# PCB_v1.net
KiCad netlist of a schematic drawn in EAGLE
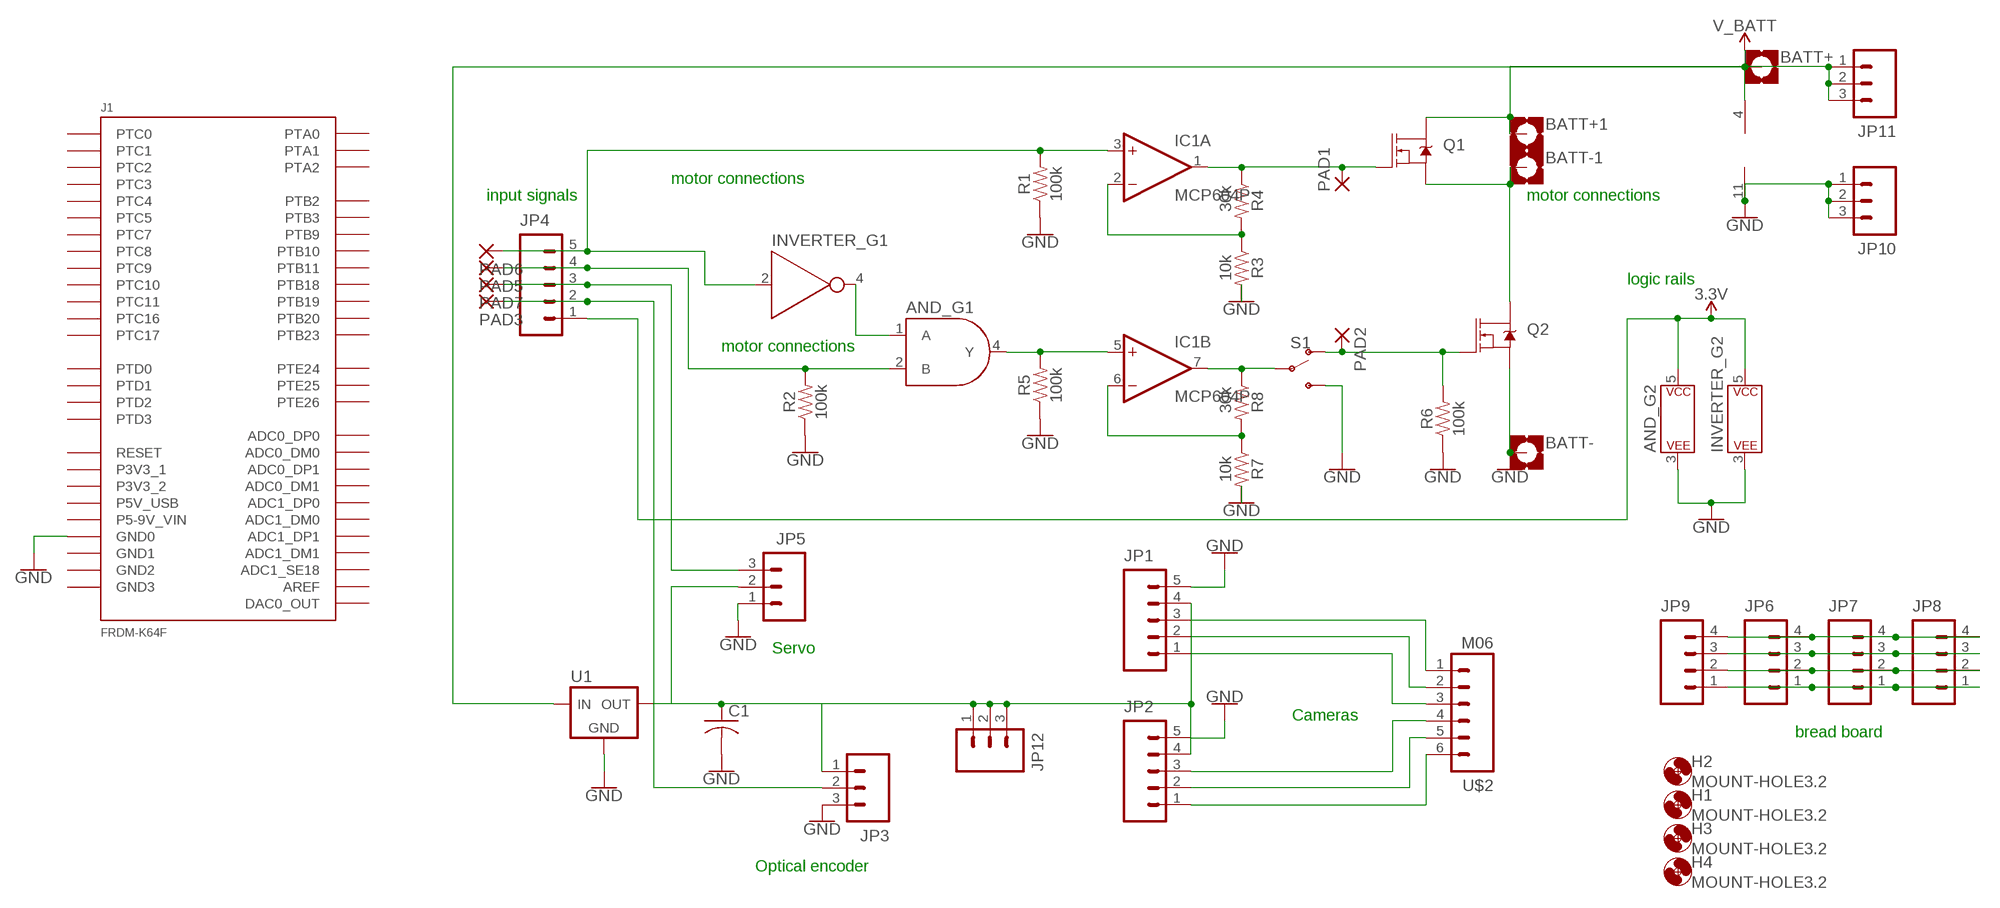
[diagram p0: schematic, sheet 1]

(export (version "E")
  (design (tool "Eeschema 10.0.6"))
  (components
    (comp (ref "AND_")
      (value "74LVC08SE")
      (footprint "eagle-import:SOT23-5")
      (libsource (lib "eagle-import") (part "7408SELVC"))
    )
    (comp (ref "BATT+")
      (value "MOUNT-PAD-SQUARE3.0")
      (footprint "eagle-import:3,0-PAD-SQUARE")
      (libsource (lib "eagle-import") (part "MOUNT-PAD-SQUARE3.0"))
    )
    (comp (ref "BATT+1")
      (value "MOUNT-PAD-SQUARE3.0")
      (footprint "eagle-import:3,0-PAD-SQUARE")
      (libsource (lib "eagle-import") (part "MOUNT-PAD-SQUARE3.0"))
    )
    (comp (ref "BATT-")
      (value "MOUNT-PAD-SQUARE3.0")
      (footprint "eagle-import:3,0-PAD-SQUARE")
      (libsource (lib "eagle-import") (part "MOUNT-PAD-SQUARE3.0"))
    )
    (comp (ref "BATT-1")
      (value "MOUNT-PAD-SQUARE3.0")
      (footprint "eagle-import:3,0-PAD-SQUARE")
      (libsource (lib "eagle-import") (part "MOUNT-PAD-SQUARE3.0"))
    )
    (comp (ref "C1")
      (value "C-075PTH")
      (footprint "eagle-import:C075")
      (libsource (lib "eagle-import") (part "C-075PTH"))
    )
    (comp (ref "H1")
      (value "MOUNT-HOLE3.2")
      (footprint "eagle-import:3,2")
      (libsource (lib "eagle-import") (part "MOUNT-HOLE3.2"))
    )
    (comp (ref "H2")
      (value "MOUNT-HOLE3.2")
      (footprint "eagle-import:3,2")
      (libsource (lib "eagle-import") (part "MOUNT-HOLE3.2"))
    )
    (comp (ref "H3")
      (value "MOUNT-HOLE3.2")
      (footprint "eagle-import:3,2")
      (libsource (lib "eagle-import") (part "MOUNT-HOLE3.2"))
    )
    (comp (ref "H4")
      (value "MOUNT-HOLE3.2")
      (footprint "eagle-import:3,2")
      (libsource (lib "eagle-import") (part "MOUNT-HOLE3.2"))
    )
    (comp (ref "IC1")
      (value "MCP604P")
      (footprint "eagle-import:DIL14")
      (libsource (lib "eagle-import") (part "MCP604P"))
    )
    (comp (ref "INVERTER_")
      (value "74HC1G04")
      (footprint "eagle-import:SOT353")
      (libsource (lib "eagle-import") (part "741G04HC"))
    )
    (comp (ref "J1")
      (value "FRDM-K64F")
      (footprint "eagle-import:FRDM-K64F")
      (libsource (lib "eagle-import") (part "FRDM-K64F"))
    )
    (comp (ref "JP1")
      (value "M05PTH")
      (footprint "eagle-import:1X05")
      (libsource (lib "eagle-import") (part "M05PTH"))
    )
    (comp (ref "JP2")
      (value "M05PTH")
      (footprint "eagle-import:1X05")
      (libsource (lib "eagle-import") (part "M05PTH"))
    )
    (comp (ref "JP3")
      (value "M03PTH")
      (footprint "eagle-import:1X03")
      (libsource (lib "eagle-import") (part "M03PTH"))
    )
    (comp (ref "JP4")
      (value "M05PTH")
      (footprint "eagle-import:1X05")
      (libsource (lib "eagle-import") (part "M05PTH"))
    )
    (comp (ref "JP5")
      (value "M03PTH")
      (footprint "eagle-import:1X03")
      (libsource (lib "eagle-import") (part "M03PTH"))
    )
    (comp (ref "JP6")
      (value "M04PTH")
      (footprint "eagle-import:1X04")
      (libsource (lib "eagle-import") (part "M04PTH"))
    )
    (comp (ref "JP7")
      (value "M04PTH")
      (footprint "eagle-import:1X04")
      (libsource (lib "eagle-import") (part "M04PTH"))
    )
    (comp (ref "JP8")
      (value "M04PTH")
      (footprint "eagle-import:1X04")
      (libsource (lib "eagle-import") (part "M04PTH"))
    )
    (comp (ref "JP9")
      (value "M04PTH")
      (footprint "eagle-import:1X04")
      (libsource (lib "eagle-import") (part "M04PTH"))
    )
    (comp (ref "JP10")
      (value "M03PTH")
      (footprint "eagle-import:1X03")
      (libsource (lib "eagle-import") (part "M03PTH"))
    )
    (comp (ref "JP11")
      (value "M03PTH")
      (footprint "eagle-import:1X03")
      (libsource (lib "eagle-import") (part "M03PTH"))
    )
    (comp (ref "JP12")
      (value "M03PTH")
      (footprint "eagle-import:1X03")
      (libsource (lib "eagle-import") (part "M03PTH"))
    )
    (comp (ref "PAD1")
      (value "2,15/1,0")
      (footprint "eagle-import:2,15_1,0")
      (libsource (lib "eagle-import") (part "2,15/1,0"))
    )
    (comp (ref "PAD2")
      (value "2,15/1,0")
      (footprint "eagle-import:2,15_1,0")
      (libsource (lib "eagle-import") (part "2,15/1,0"))
    )
    (comp (ref "PAD3")
      (value "2,15/1,0")
      (footprint "eagle-import:2,15_1,0")
      (libsource (lib "eagle-import") (part "2,15/1,0"))
    )
    (comp (ref "PAD5")
      (value "2,15/1,0")
      (footprint "eagle-import:2,15_1,0")
      (libsource (lib "eagle-import") (part "2,15/1,0"))
    )
    (comp (ref "PAD6")
      (value "2,15/1,0")
      (footprint "eagle-import:2,15_1,0")
      (libsource (lib "eagle-import") (part "2,15/1,0"))
    )
    (comp (ref "PAD7")
      (value "2,15/1,0")
      (footprint "eagle-import:2,15_1,0")
      (libsource (lib "eagle-import") (part "2,15/1,0"))
    )
    (comp (ref "Q1")
      (value "MOSFET-NCH-FQP30N06L")
      (footprint "eagle-import:TO220V")
      (libsource (lib "eagle-import") (part "MOSFET-NCH-FQP30N06L"))
    )
    (comp (ref "Q2")
      (value "MOSFET-NCH-FQP30N06L")
      (footprint "eagle-import:TO220V")
      (libsource (lib "eagle-import") (part "MOSFET-NCH-FQP30N06L"))
    )
    (comp (ref "R1")
      (value "100k")
      (footprint "eagle-import:AXIAL-0.3")
      (libsource (lib "eagle-import") (part "10KOHM-HORIZ-1/4W-1%"))
    )
    (comp (ref "R2")
      (value "100k")
      (footprint "eagle-import:AXIAL-0.3")
      (libsource (lib "eagle-import") (part "10KOHM-HORIZ-1/4W-1%"))
    )
    (comp (ref "R3")
      (value "10k")
      (footprint "eagle-import:AXIAL-0.3")
      (libsource (lib "eagle-import") (part "10KOHM-HORIZ-1/4W-1%"))
    )
    (comp (ref "R4")
      (value "30k")
      (footprint "eagle-import:AXIAL-0.3")
      (libsource (lib "eagle-import") (part "RESISTORAXIAL-0.3"))
    )
    (comp (ref "R5")
      (value "100k")
      (footprint "eagle-import:AXIAL-0.3")
      (libsource (lib "eagle-import") (part "10KOHM-HORIZ-1/4W-1%"))
    )
    (comp (ref "R6")
      (value "100k")
      (footprint "eagle-import:AXIAL-0.3")
      (libsource (lib "eagle-import") (part "10KOHM-HORIZ-1/4W-1%"))
    )
    (comp (ref "R7")
      (value "10k")
      (footprint "eagle-import:AXIAL-0.3")
      (libsource (lib "eagle-import") (part "10KOHM-HORIZ-1/4W-1%"))
    )
    (comp (ref "R8")
      (value "30k")
      (footprint "eagle-import:AXIAL-0.3")
      (libsource (lib "eagle-import") (part "RESISTORAXIAL-0.3"))
    )
    (comp (ref "S1")
      (value "SWITCH-SPDT-PTH-11.6X4.0MM-KIT")
      (footprint "eagle-import:SWITCH_SPDT_PTH_11.6X4.0MM_KIT")
      (libsource (lib "eagle-import") (part "SWITCH-SPDT-PTH-11.6X4.0MM-KIT"))
    )
    (comp (ref "U$2")
      (value "M06")
      (footprint "eagle-import:1X06-MTA")
      (libsource (lib "eagle-import") (part "M06"))
    )
    (comp (ref "U1")
      (value "78XX-TO220V")
      (footprint "eagle-import:TO220BV")
      (libsource (lib "eagle-import") (part "78XX-TO220V"))
    )
  )
  (nets
    (net (code "1") (name "3.3V") (class "Default")
      (node (ref "AND_") (pin "5") (pinfunction "P$V+_5") (pintype "bidirectional"))
      (node (ref "INVERTER_") (pin "5") (pinfunction "P$V+_5") (pintype "bidirectional"))
      (node (ref "JP4") (pin "1") (pinfunction "1_1") (pintype "passive"))
    )
    (net (code "2") (name "GND") (class "Default")
      (node (ref "AND_") (pin "3") (pinfunction "P$V-_3") (pintype "bidirectional"))
      (node (ref "BATT-") (pin "B3,0") (pinfunction "MOUNT_B3,0") (pintype "passive"))
      (node (ref "C1") (pin "2") (pinfunction "-_2") (pintype "passive"))
      (node (ref "IC1") (pin "11") (pinfunction "V-_11") (pintype "power_in"))
      (node (ref "INVERTER_") (pin "3") (pinfunction "P$V-_3") (pintype "bidirectional"))
      (node (ref "J1") (pin "J2-3") (pinfunction "GND0_J2-3") (pintype "bidirectional"))
      (node (ref "JP1") (pin "5") (pinfunction "5_5") (pintype "passive"))
      (node (ref "JP10") (pin "1") (pinfunction "1_1") (pintype "passive"))
      (node (ref "JP10") (pin "2") (pinfunction "2_2") (pintype "passive"))
      (node (ref "JP10") (pin "3") (pinfunction "3_3") (pintype "passive"))
      (node (ref "JP2") (pin "5") (pinfunction "5_5") (pintype "passive"))
      (node (ref "JP3") (pin "3") (pinfunction "3_3") (pintype "passive"))
      (node (ref "JP5") (pin "1") (pinfunction "1_1") (pintype "passive"))
      (node (ref "Q2") (pin "3") (pinfunction "S_3") (pintype "bidirectional"))
      (node (ref "R1") (pin "P$1") (pinfunction "1_P$1") (pintype "passive"))
      (node (ref "R2") (pin "P$1") (pinfunction "1_P$1") (pintype "passive"))
      (node (ref "R3") (pin "P$2") (pinfunction "2_P$2") (pintype "passive"))
      (node (ref "R5") (pin "P$1") (pinfunction "1_P$1") (pintype "passive"))
      (node (ref "R6") (pin "P$1") (pinfunction "1_P$1") (pintype "passive"))
      (node (ref "R7") (pin "P$2") (pinfunction "2_P$2") (pintype "passive"))
      (node (ref "S1") (pin "3") (pinfunction "S_3") (pintype "passive"))
      (node (ref "U1") (pin "2") (pinfunction "GND_2") (pintype "power_in"))
    )
    (net (code "3") (name "Net-(AND_A-A)") (class "Default")
      (node (ref "AND_") (pin "1") (pinfunction "A_1") (pintype "bidirectional"))
      (node (ref "INVERTER_") (pin "4") (pinfunction "Y_4") (pintype "bidirectional"))
    )
    (net (code "4") (name "Net-(AND_A-B)") (class "Default")
      (node (ref "AND_") (pin "2") (pinfunction "B_2") (pintype "bidirectional"))
      (node (ref "JP4") (pin "4") (pinfunction "4_4") (pintype "passive"))
      (node (ref "PAD5") (pin "1") (pinfunction "P_1") (pintype "passive"))
      (node (ref "R2") (pin "P$2") (pinfunction "2_P$2") (pintype "passive"))
    )
    (net (code "5") (name "Net-(AND_A-Y)") (class "Default")
      (node (ref "AND_") (pin "4") (pinfunction "Y_4") (pintype "bidirectional"))
      (node (ref "IC1") (pin "5") (pinfunction "+IN_5") (pintype "input"))
      (node (ref "R5") (pin "P$2") (pinfunction "2_P$2") (pintype "passive"))
    )
    (net (code "6") (name "Net-(BATT-1-MOUNT)") (class "Default")
      (node (ref "BATT-1") (pin "B3,0") (pinfunction "MOUNT_B3,0") (pintype "passive"))
      (node (ref "Q1") (pin "3") (pinfunction "S_3") (pintype "bidirectional"))
      (node (ref "Q2") (pin "2") (pinfunction "D_2") (pintype "bidirectional"))
    )
    (net (code "7") (name "Net-(C1-+)") (class "Default")
      (node (ref "C1") (pin "1") (pinfunction "+_1") (pintype "passive"))
      (node (ref "JP1") (pin "4") (pinfunction "4_4") (pintype "passive"))
      (node (ref "JP12") (pin "1") (pinfunction "1_1") (pintype "passive"))
      (node (ref "JP12") (pin "2") (pinfunction "2_2") (pintype "passive"))
      (node (ref "JP12") (pin "3") (pinfunction "3_3") (pintype "passive"))
      (node (ref "JP2") (pin "4") (pinfunction "4_4") (pintype "passive"))
      (node (ref "JP3") (pin "1") (pinfunction "1_1") (pintype "passive"))
      (node (ref "U1") (pin "3") (pinfunction "VOUT_3") (pintype "power_in"))
    )
    (net (code "8") (name "Net-(IC1A-+IN)") (class "Default")
      (node (ref "IC1") (pin "3") (pinfunction "+IN_3") (pintype "input"))
      (node (ref "INVERTER_") (pin "2") (pinfunction "A_2") (pintype "bidirectional"))
      (node (ref "JP4") (pin "5") (pinfunction "5_5") (pintype "passive"))
      (node (ref "PAD6") (pin "1") (pinfunction "P_1") (pintype "passive"))
      (node (ref "R1") (pin "P$2") (pinfunction "2_P$2") (pintype "passive"))
    )
    (net (code "9") (name "Net-(IC1A--IN)") (class "Default")
      (node (ref "IC1") (pin "2") (pinfunction "-IN_2") (pintype "input"))
      (node (ref "R3") (pin "P$1") (pinfunction "1_P$1") (pintype "passive"))
      (node (ref "R4") (pin "P$2") (pinfunction "2_P$2") (pintype "passive"))
    )
    (net (code "10") (name "Net-(IC1A-OUT)") (class "Default")
      (node (ref "IC1") (pin "1") (pinfunction "OUT_1") (pintype "output"))
      (node (ref "PAD1") (pin "1") (pinfunction "P_1") (pintype "passive"))
      (node (ref "Q1") (pin "1") (pinfunction "G_1") (pintype "bidirectional"))
      (node (ref "R4") (pin "P$1") (pinfunction "1_P$1") (pintype "passive"))
    )
    (net (code "11") (name "Net-(IC1B--IN)") (class "Default")
      (node (ref "IC1") (pin "6") (pinfunction "-IN_6") (pintype "input"))
      (node (ref "R7") (pin "P$1") (pinfunction "1_P$1") (pintype "passive"))
      (node (ref "R8") (pin "P$2") (pinfunction "2_P$2") (pintype "passive"))
    )
    (net (code "12") (name "Net-(IC1B-OUT)") (class "Default")
      (node (ref "IC1") (pin "7") (pinfunction "OUT_7") (pintype "output"))
      (node (ref "R8") (pin "P$1") (pinfunction "1_P$1") (pintype "passive"))
      (node (ref "S1") (pin "2") (pinfunction "P_2") (pintype "passive"))
    )
    (net (code "13") (name "Net-(JP1-Pad1)") (class "Default")
      (node (ref "JP1") (pin "1") (pinfunction "1_1") (pintype "passive"))
      (node (ref "U$2") (pin "3") (pinfunction "3_3") (pintype "passive"))
    )
    (net (code "14") (name "Net-(JP1-Pad2)") (class "Default")
      (node (ref "JP1") (pin "2") (pinfunction "2_2") (pintype "passive"))
      (node (ref "U$2") (pin "2") (pinfunction "2_2") (pintype "passive"))
    )
    (net (code "15") (name "Net-(JP1-Pad3)") (class "Default")
      (node (ref "JP1") (pin "3") (pinfunction "3_3") (pintype "passive"))
      (node (ref "U$2") (pin "1") (pinfunction "1_1") (pintype "passive"))
    )
    (net (code "16") (name "Net-(JP2-Pad1)") (class "Default")
      (node (ref "JP2") (pin "1") (pinfunction "1_1") (pintype "passive"))
      (node (ref "U$2") (pin "6") (pinfunction "6_6") (pintype "passive"))
    )
    (net (code "17") (name "Net-(JP2-Pad2)") (class "Default")
      (node (ref "JP2") (pin "2") (pinfunction "2_2") (pintype "passive"))
      (node (ref "U$2") (pin "5") (pinfunction "5_5") (pintype "passive"))
    )
    (net (code "18") (name "Net-(JP2-Pad3)") (class "Default")
      (node (ref "JP2") (pin "3") (pinfunction "3_3") (pintype "passive"))
      (node (ref "U$2") (pin "4") (pinfunction "4_4") (pintype "passive"))
    )
    (net (code "19") (name "Net-(JP6-Pad1)") (class "Default")
      (node (ref "JP6") (pin "1") (pinfunction "1_1") (pintype "passive"))
      (node (ref "JP7") (pin "1") (pinfunction "1_1") (pintype "passive"))
      (node (ref "JP8") (pin "1") (pinfunction "1_1") (pintype "passive"))
      (node (ref "JP9") (pin "1") (pinfunction "1_1") (pintype "passive"))
    )
    (net (code "20") (name "Net-(JP6-Pad2)") (class "Default")
      (node (ref "JP6") (pin "2") (pinfunction "2_2") (pintype "passive"))
      (node (ref "JP7") (pin "2") (pinfunction "2_2") (pintype "passive"))
      (node (ref "JP8") (pin "2") (pinfunction "2_2") (pintype "passive"))
      (node (ref "JP9") (pin "2") (pinfunction "2_2") (pintype "passive"))
    )
    (net (code "21") (name "Net-(JP6-Pad3)") (class "Default")
      (node (ref "JP6") (pin "3") (pinfunction "3_3") (pintype "passive"))
      (node (ref "JP7") (pin "3") (pinfunction "3_3") (pintype "passive"))
      (node (ref "JP8") (pin "3") (pinfunction "3_3") (pintype "passive"))
      (node (ref "JP9") (pin "3") (pinfunction "3_3") (pintype "passive"))
    )
    (net (code "22") (name "Net-(JP6-Pad4)") (class "Default")
      (node (ref "JP6") (pin "4") (pinfunction "4_4") (pintype "passive"))
      (node (ref "JP7") (pin "4") (pinfunction "4_4") (pintype "passive"))
      (node (ref "JP8") (pin "4") (pinfunction "4_4") (pintype "passive"))
      (node (ref "JP9") (pin "4") (pinfunction "4_4") (pintype "passive"))
    )
    (net (code "23") (name "Net-(PAD2-P)") (class "Default")
      (node (ref "PAD2") (pin "1") (pinfunction "P_1") (pintype "passive"))
      (node (ref "Q2") (pin "1") (pinfunction "G_1") (pintype "bidirectional"))
      (node (ref "R6") (pin "P$2") (pinfunction "2_P$2") (pintype "passive"))
      (node (ref "S1") (pin "1") (pinfunction "O_1") (pintype "passive"))
    )
    (net (code "24") (name "Net-(PAD3-P)") (class "Default")
      (node (ref "JP3") (pin "2") (pinfunction "2_2") (pintype "passive"))
      (node (ref "JP4") (pin "2") (pinfunction "2_2") (pintype "passive"))
      (node (ref "PAD3") (pin "1") (pinfunction "P_1") (pintype "passive"))
    )
    (net (code "25") (name "Net-(PAD7-P)") (class "Default")
      (node (ref "JP4") (pin "3") (pinfunction "3_3") (pintype "passive"))
      (node (ref "JP5") (pin "3") (pinfunction "3_3") (pintype "passive"))
      (node (ref "PAD7") (pin "1") (pinfunction "P_1") (pintype "passive"))
    )
    (net (code "26") (name "V_BATT") (class "Default")
      (node (ref "BATT+") (pin "B3,0") (pinfunction "MOUNT_B3,0") (pintype "passive"))
      (node (ref "BATT+1") (pin "B3,0") (pinfunction "MOUNT_B3,0") (pintype "passive"))
      (node (ref "IC1") (pin "4") (pinfunction "V+_4") (pintype "power_in"))
      (node (ref "JP11") (pin "1") (pinfunction "1_1") (pintype "passive"))
      (node (ref "JP11") (pin "2") (pinfunction "2_2") (pintype "passive"))
      (node (ref "JP11") (pin "3") (pinfunction "3_3") (pintype "passive"))
      (node (ref "Q1") (pin "2") (pinfunction "D_2") (pintype "bidirectional"))
      (node (ref "U1") (pin "1") (pinfunction "VIN_1") (pintype "power_in"))
    )
    (net (code "27") (name "unconnected-(J1-ADC0_DM0-PadJ2-7)") (class "Default")
      (node (ref "J1") (pin "J2-7") (pinfunction "ADC0_DM0_J2-7") (pintype "bidirectional"))
    )
    (net (code "28") (name "unconnected-(J1-ADC0_DM1-PadJ4-3)") (class "Default")
      (node (ref "J1") (pin "J4-3") (pinfunction "ADC0_DM1_J4-3") (pintype "bidirectional"))
    )
    (net (code "29") (name "unconnected-(J1-ADC0_DP0-PadJ2-5)") (class "Default")
      (node (ref "J1") (pin "J2-5") (pinfunction "ADC0_DP0_J2-5") (pintype "bidirectional"))
    )
    (net (code "30") (name "unconnected-(J1-ADC0_DP1-PadJ4-1)") (class "Default")
      (node (ref "J1") (pin "J4-1") (pinfunction "ADC0_DP1_J4-1") (pintype "bidirectional"))
    )
    (net (code "31") (name "unconnected-(J1-ADC1_DM0-PadJ2-13)") (class "Default")
      (node (ref "J1") (pin "J2-13") (pinfunction "ADC1_DM0_J2-13") (pintype "bidirectional"))
    )
    (net (code "32") (name "unconnected-(J1-ADC1_DM1-PadJ4-7)") (class "Default")
      (node (ref "J1") (pin "J4-7") (pinfunction "ADC1_DM1_J4-7") (pintype "bidirectional"))
    )
    (net (code "33") (name "unconnected-(J1-ADC1_DP0-PadJ2-11)") (class "Default")
      (node (ref "J1") (pin "J2-11") (pinfunction "ADC1_DP0_J2-11") (pintype "bidirectional"))
    )
    (net (code "34") (name "unconnected-(J1-ADC1_DP1-PadJ4-5)") (class "Default")
      (node (ref "J1") (pin "J4-5") (pinfunction "ADC1_DP1_J4-5") (pintype "bidirectional"))
    )
    (net (code "35") (name "unconnected-(J1-ADC1_SE18-PadJ2-17)") (class "Default")
      (node (ref "J1") (pin "J2-17") (pinfunction "ADC1_SE18_J2-17") (pintype "bidirectional"))
    )
    (net (code "36") (name "unconnected-(J1-AREF-PadJ2-16)") (class "Default")
      (node (ref "J1") (pin "J2-16") (pinfunction "AREF_J2-16") (pintype "bidirectional"))
    )
    (net (code "37") (name "unconnected-(J1-DAC0_OUT-PadJ4-11)") (class "Default")
      (node (ref "J1") (pin "J4-11") (pinfunction "DAC0_OUT_J4-11") (pintype "bidirectional"))
    )
    (net (code "38") (name "unconnected-(J1-GND1-PadJ2-14)") (class "Default")
      (node (ref "J1") (pin "J2-14") (pinfunction "GND1_J2-14") (pintype "bidirectional"))
    )
    (net (code "39") (name "unconnected-(J1-GND2-PadJ3-12)") (class "Default")
      (node (ref "J1") (pin "J3-12") (pinfunction "GND2_J3-12") (pintype "bidirectional"))
    )
    (net (code "40") (name "unconnected-(J1-GND3-PadJ3-14)") (class "Default")
      (node (ref "J1") (pin "J3-14") (pinfunction "GND3_J3-14") (pintype "bidirectional"))
    )
    (net (code "41") (name "unconnected-(J1-P3V3_1-PadJ3-4)") (class "Default")
      (node (ref "J1") (pin "J3-4") (pinfunction "P3V3_1_J3-4") (pintype "bidirectional"))
    )
    (net (code "42") (name "unconnected-(J1-P3V3_2-PadJ3-8)") (class "Default")
      (node (ref "J1") (pin "J3-8") (pinfunction "P3V3_2_J3-8") (pintype "bidirectional"))
    )
    (net (code "43") (name "unconnected-(J1-P5-9V_VIN-PadJ3-16)") (class "Default")
      (node (ref "J1") (pin "J3-16") (pinfunction "P5-9V_VIN_J3-16") (pintype "bidirectional"))
    )
    (net (code "44") (name "unconnected-(J1-P5V_USB-PadJ3-10)") (class "Default")
      (node (ref "J1") (pin "J3-10") (pinfunction "P5V_USB_J3-10") (pintype "bidirectional"))
    )
    (net (code "45") (name "unconnected-(J1-PTA0-PadJ2-2)") (class "Default")
      (node (ref "J1") (pin "J2-2") (pinfunction "PTA0_J2-2") (pintype "bidirectional"))
    )
    (net (code "46") (name "unconnected-(J1-PTA1-PadJ1-8)") (class "Default")
      (node (ref "J1") (pin "J1-8") (pinfunction "PTA1_J1-8") (pintype "bidirectional"))
    )
    (net (code "47") (name "unconnected-(J1-PTA2-PadJ1-12)") (class "Default")
      (node (ref "J1") (pin "J1-12") (pinfunction "PTA2_J1-12") (pintype "bidirectional"))
    )
    (net (code "48") (name "unconnected-(J1-PTB2-PadJ4-2)") (class "Default")
      (node (ref "J1") (pin "J4-2") (pinfunction "PTB2_J4-2") (pintype "bidirectional"))
    )
    (net (code "49") (name "unconnected-(J1-PTB3-PadJ4-4)") (class "Default")
      (node (ref "J1") (pin "J4-4") (pinfunction "PTB3_J4-4") (pintype "bidirectional"))
    )
    (net (code "50") (name "unconnected-(J1-PTB9-PadJ1-6)") (class "Default")
      (node (ref "J1") (pin "J1-6") (pinfunction "PTB9_J1-6") (pintype "bidirectional"))
    )
    (net (code "51") (name "unconnected-(J1-PTB10-PadJ4-6)") (class "Default")
      (node (ref "J1") (pin "J4-6") (pinfunction "PTB10_J4-6") (pintype "bidirectional"))
    )
    (net (code "52") (name "unconnected-(J1-PTB11-PadJ4-8)") (class "Default")
      (node (ref "J1") (pin "J4-8") (pinfunction "PTB11_J4-8") (pintype "bidirectional"))
    )
    (net (code "53") (name "unconnected-(J1-PTB18-PadJ1-1)") (class "Default")
      (node (ref "J1") (pin "J1-1") (pinfunction "PTB18_J1-1") (pintype "bidirectional"))
    )
    (net (code "54") (name "unconnected-(J1-PTB19-PadJ1-3)") (class "Default")
      (node (ref "J1") (pin "J1-3") (pinfunction "PTB19_J1-3") (pintype "bidirectional"))
    )
    (net (code "55") (name "unconnected-(J1-PTB20-PadJ4-9)") (class "Default")
      (node (ref "J1") (pin "J4-9") (pinfunction "PTB20_J4-9") (pintype "bidirectional"))
    )
    (net (code "56") (name "unconnected-(J1-PTB23-PadJ1-10)") (class "Default")
      (node (ref "J1") (pin "J1-10") (pinfunction "PTB23_J1-10") (pintype "bidirectional"))
    )
    (net (code "57") (name "unconnected-(J1-PTC0-PadJ1-11)") (class "Default")
      (node (ref "J1") (pin "J1-11") (pinfunction "PTC0_J1-11") (pintype "bidirectional"))
    )
    (net (code "58") (name "unconnected-(J1-PTC1-PadJ1-5)") (class "Default")
      (node (ref "J1") (pin "J1-5") (pinfunction "PTC1_J1-5") (pintype "bidirectional"))
    )
    (net (code "59") (name "unconnected-(J1-PTC2-PadJ1-14)") (class "Default")
      (node (ref "J1") (pin "J1-14") (pinfunction "PTC2_J1-14") (pintype "bidirectional"))
    )
    (net (code "60") (name "unconnected-(J1-PTC3-PadJ1-16)") (class "Default")
      (node (ref "J1") (pin "J1-16") (pinfunction "PTC3_J1-16") (pintype "bidirectional"))
    )
    (net (code "61") (name "unconnected-(J1-PTC4-PadJ2-4)") (class "Default")
      (node (ref "J1") (pin "J2-4") (pinfunction "PTC4_J2-4") (pintype "bidirectional"))
    )
    (net (code "62") (name "unconnected-(J1-PTC5-PadJ1-15)") (class "Default")
      (node (ref "J1") (pin "J1-15") (pinfunction "PTC5_J1-15") (pintype "bidirectional"))
    )
    (net (code "63") (name "unconnected-(J1-PTC7-PadJ1-13)") (class "Default")
      (node (ref "J1") (pin "J1-13") (pinfunction "PTC7_J1-13") (pintype "bidirectional"))
    )
    (net (code "64") (name "unconnected-(J1-PTC8-PadJ1-7)") (class "Default")
      (node (ref "J1") (pin "J1-7") (pinfunction "PTC8_J1-7") (pintype "bidirectional"))
    )
    (net (code "65") (name "unconnected-(J1-PTC9-PadJ1-9)") (class "Default")
      (node (ref "J1") (pin "J1-9") (pinfunction "PTC9_J1-9") (pintype "bidirectional"))
    )
    (net (code "66") (name "unconnected-(J1-PTC10-PadJ4-12)") (class "Default")
      (node (ref "J1") (pin "J4-12") (pinfunction "PTC10_J4-12") (pintype "bidirectional"))
    )
    (net (code "67") (name "unconnected-(J1-PTC11-PadJ4-10)") (class "Default")
      (node (ref "J1") (pin "J4-10") (pinfunction "PTC11_J4-10") (pintype "bidirectional"))
    )
    (net (code "68") (name "unconnected-(J1-PTC16-PadJ1-2)") (class "Default")
      (node (ref "J1") (pin "J1-2") (pinfunction "PTC16_J1-2") (pintype "bidirectional"))
    )
    (net (code "69") (name "unconnected-(J1-PTC17-PadJ1-4)") (class "Default")
      (node (ref "J1") (pin "J1-4") (pinfunction "PTC17_J1-4") (pintype "bidirectional"))
    )
    (net (code "70") (name "unconnected-(J1-PTD0-PadJ2-6)") (class "Default")
      (node (ref "J1") (pin "J2-6") (pinfunction "PTD0_J2-6") (pintype "bidirectional"))
    )
    (net (code "71") (name "unconnected-(J1-PTD1-PadJ2-12)") (class "Default")
      (node (ref "J1") (pin "J2-12") (pinfunction "PTD1_J2-12") (pintype "bidirectional"))
    )
    (net (code "72") (name "unconnected-(J1-PTD2-PadJ2-8)") (class "Default")
      (node (ref "J1") (pin "J2-8") (pinfunction "PTD2_J2-8") (pintype "bidirectional"))
    )
    (net (code "73") (name "unconnected-(J1-PTD3-PadJ2-10)") (class "Default")
      (node (ref "J1") (pin "J2-10") (pinfunction "PTD3_J2-10") (pintype "bidirectional"))
    )
    (net (code "74") (name "unconnected-(J1-PTE24-PadJ2-20)") (class "Default")
      (node (ref "J1") (pin "J2-20") (pinfunction "PTE24_J2-20") (pintype "bidirectional"))
    )
    (net (code "75") (name "unconnected-(J1-PTE25-PadJ2-18)") (class "Default")
      (node (ref "J1") (pin "J2-18") (pinfunction "PTE25_J2-18") (pintype "bidirectional"))
    )
    (net (code "76") (name "unconnected-(J1-PTE26-PadJ2-1)") (class "Default")
      (node (ref "J1") (pin "J2-1") (pinfunction "PTE26_J2-1") (pintype "bidirectional"))
    )
    (net (code "77") (name "unconnected-(J1-RESET-PadJ3-6)") (class "Default")
      (node (ref "J1") (pin "J3-6") (pinfunction "RESET_J3-6") (pintype "bidirectional"))
    )
    (net (code "78") (name "unconnected-(JP5-Pad2)") (class "Default")
      (node (ref "JP5") (pin "2") (pinfunction "2_2") (pintype "passive"))
    )
  )
)
